# SparkFun_AST-CAN485_IO_Shield.net
KiCad netlist of a schematic drawn in EAGLE
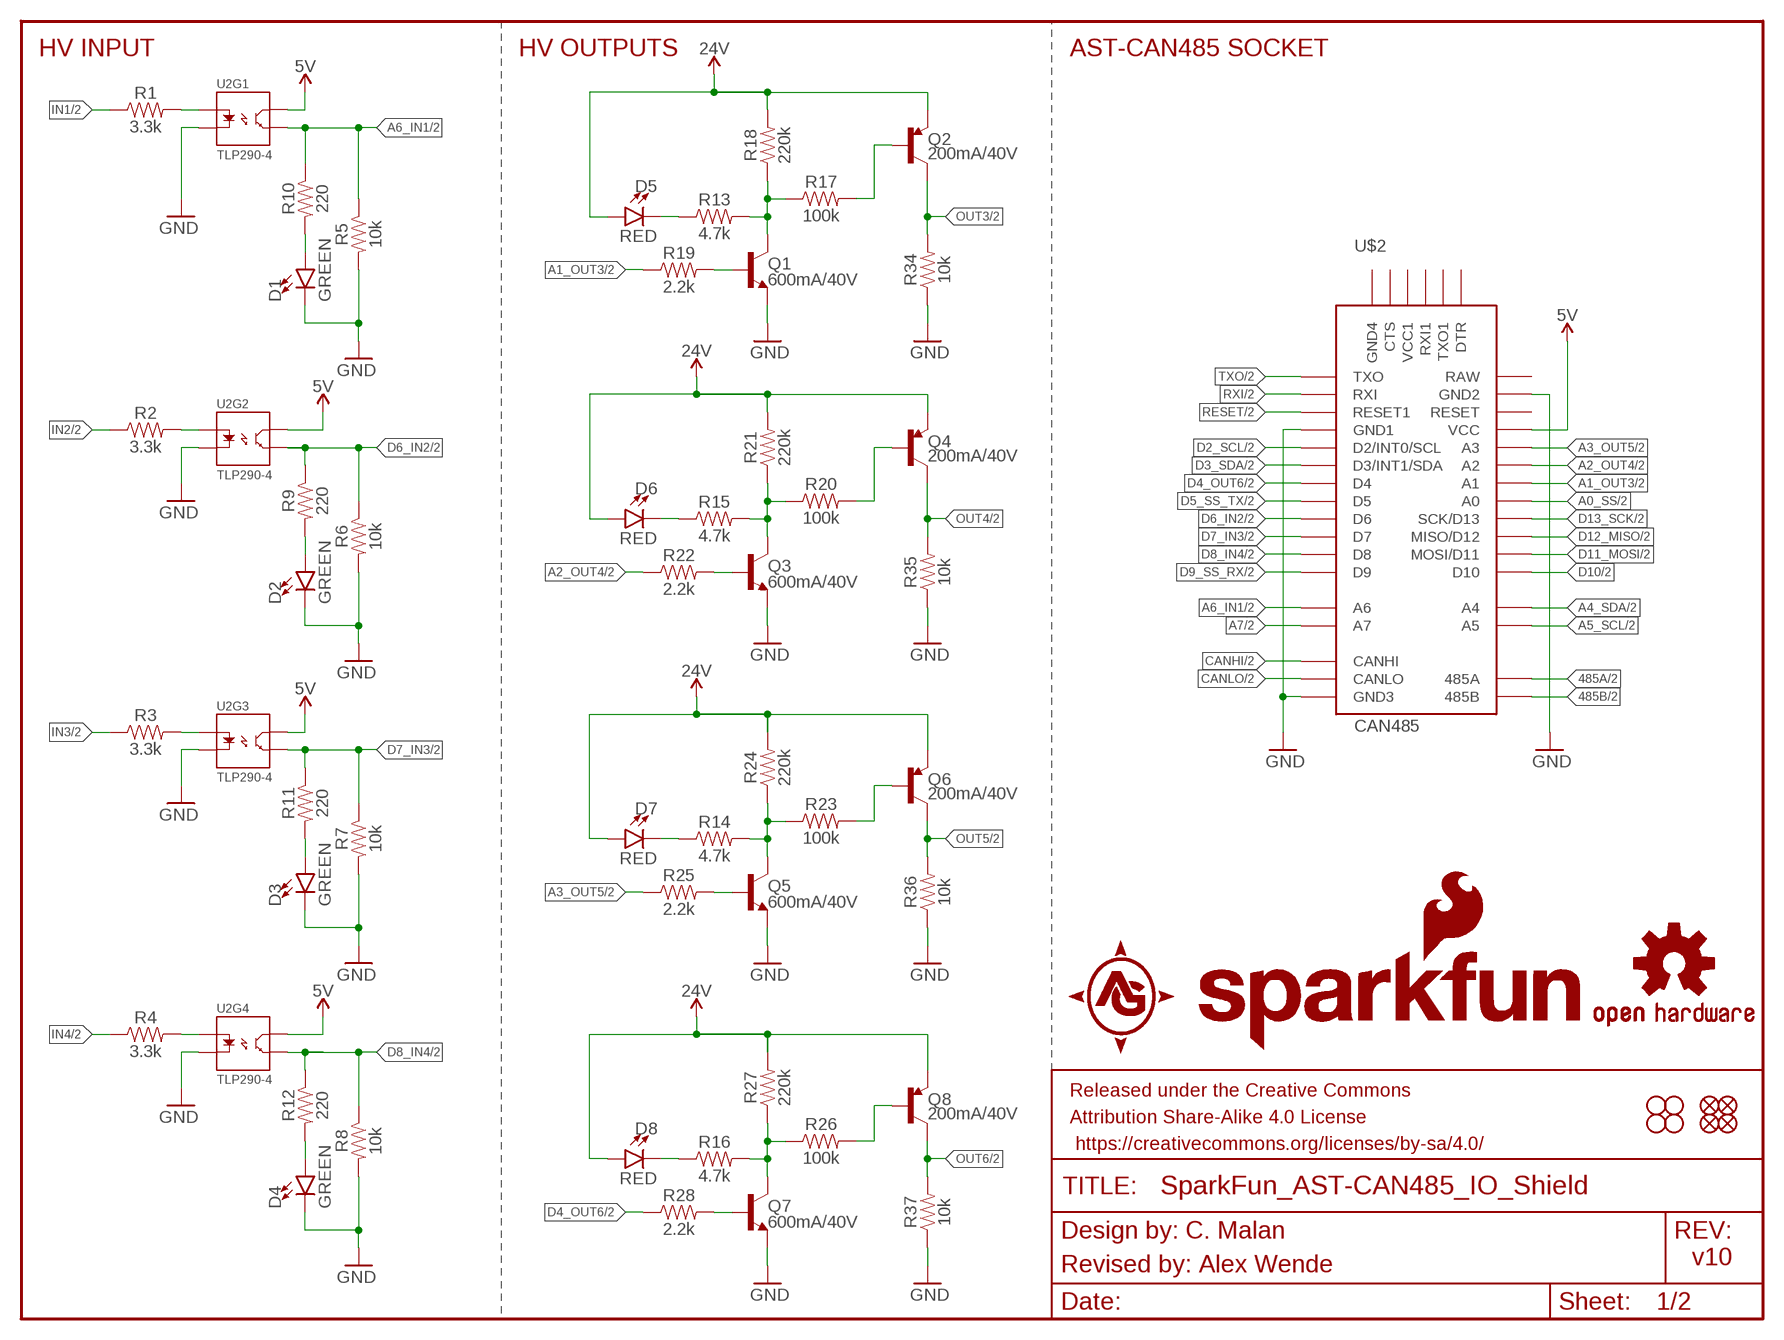
[diagram p0: schematic, sheet 1]
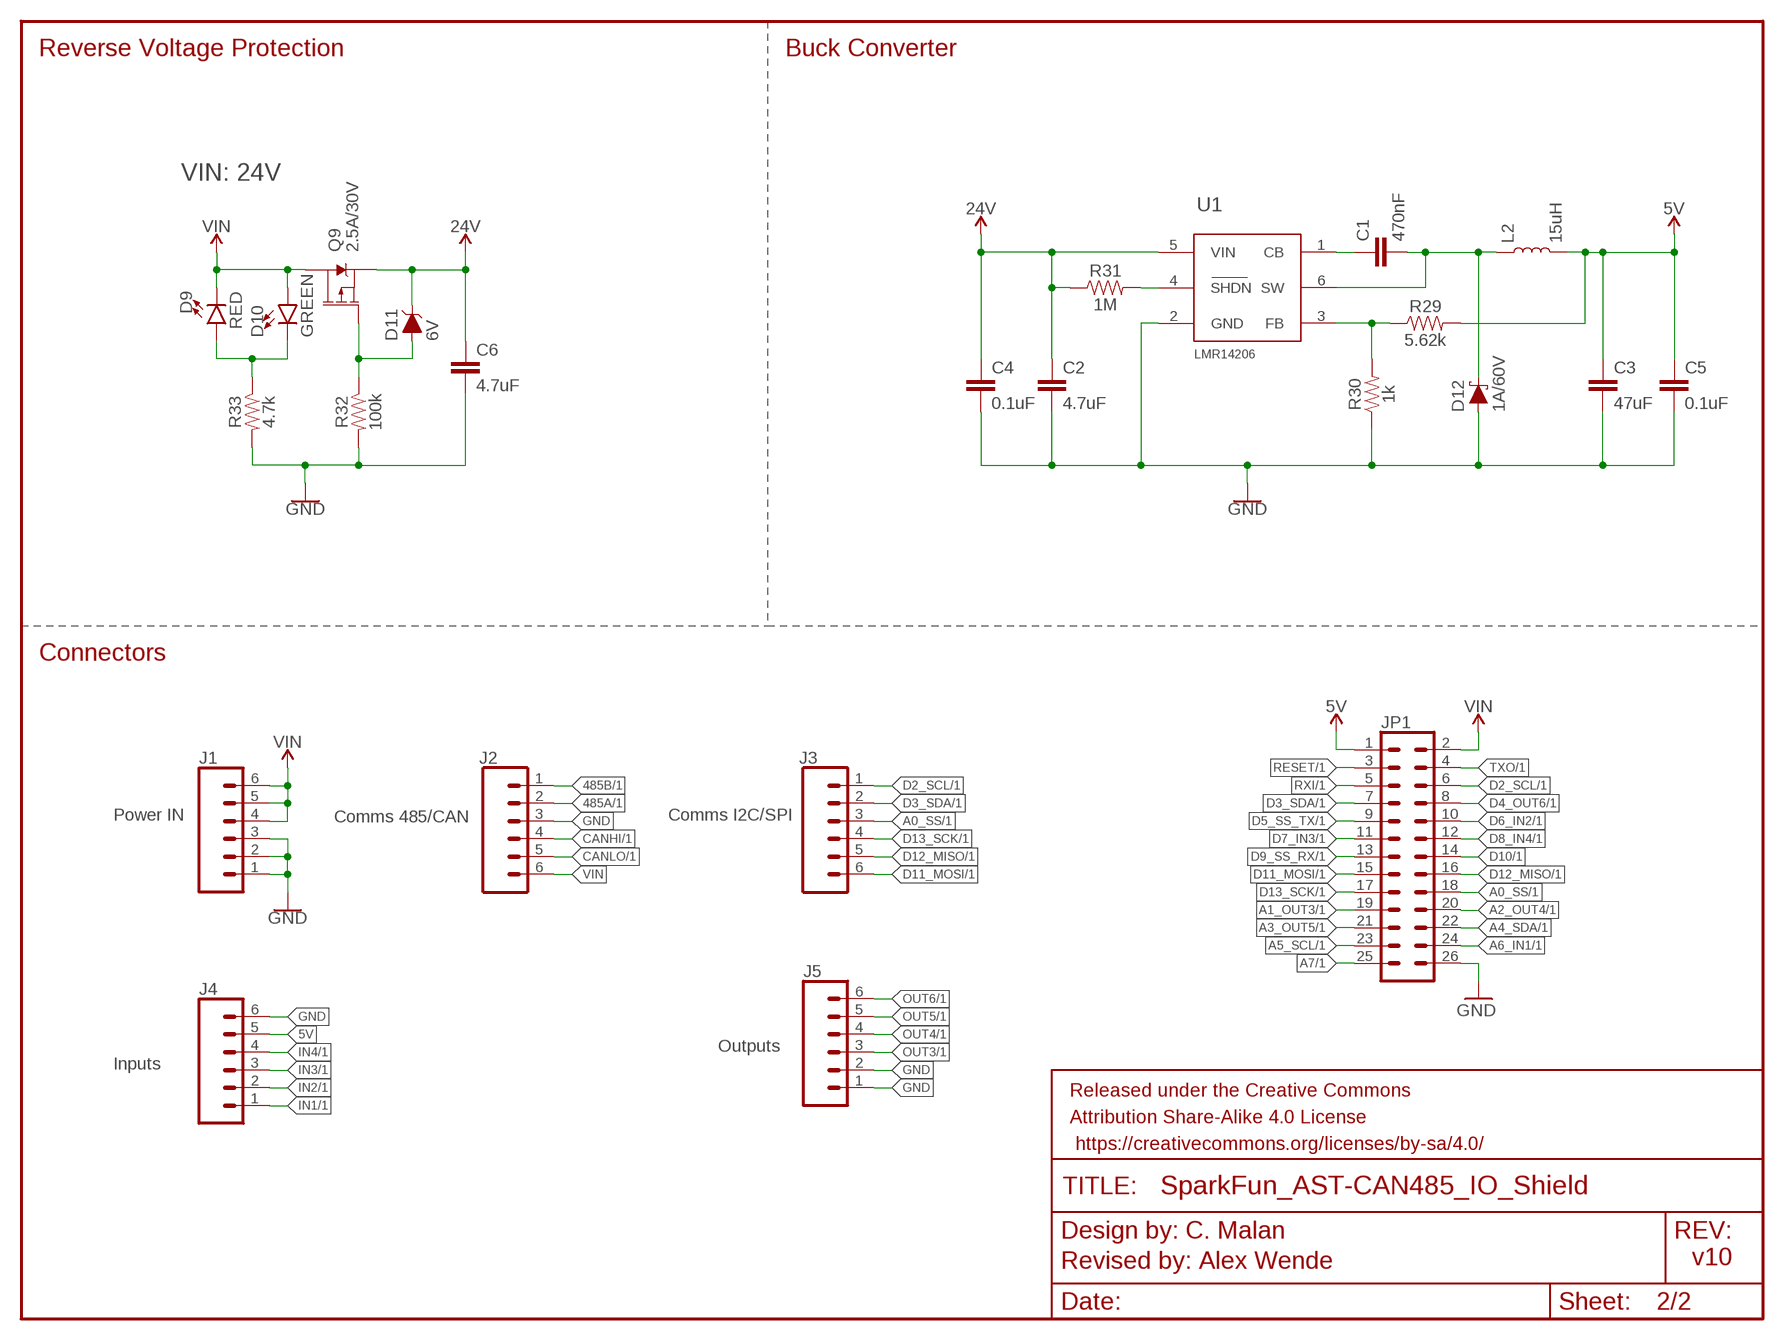
[diagram p1: schematic, sheet 2]

(export (version "E")
  (design (tool "Eeschema 10.0.6"))
  (components
    (comp (ref "D1")
      (value "GREEN")
      (footprint "eagle-import:LED-0603")
      (libsource (lib "eagle-import") (part "LED-GREEN0603"))
    )
    (comp (ref "D2")
      (value "GREEN")
      (footprint "eagle-import:LED-0603")
      (libsource (lib "eagle-import") (part "LED-GREEN0603"))
    )
    (comp (ref "D3")
      (value "GREEN")
      (footprint "eagle-import:LED-0603")
      (libsource (lib "eagle-import") (part "LED-GREEN0603"))
    )
    (comp (ref "D4")
      (value "GREEN")
      (footprint "eagle-import:LED-0603")
      (libsource (lib "eagle-import") (part "LED-GREEN0603"))
    )
    (comp (ref "D5")
      (value "RED")
      (footprint "eagle-import:LED-0603")
      (libsource (lib "eagle-import") (part "LED-RED0603"))
    )
    (comp (ref "D6")
      (value "RED")
      (footprint "eagle-import:LED-0603")
      (libsource (lib "eagle-import") (part "LED-RED0603"))
    )
    (comp (ref "D7")
      (value "RED")
      (footprint "eagle-import:LED-0603")
      (libsource (lib "eagle-import") (part "LED-RED0603"))
    )
    (comp (ref "D8")
      (value "RED")
      (footprint "eagle-import:LED-0603")
      (libsource (lib "eagle-import") (part "LED-RED0603"))
    )
    (comp (ref "FD1")
      (value "FIDUCIALUFIDUCIAL")
      (footprint "eagle-import:FIDUCIAL-MICRO")
      (libsource (lib "eagle-import") (part "FIDUCIALUFIDUCIAL"))
    )
    (comp (ref "FD2")
      (value "FIDUCIALUFIDUCIAL")
      (footprint "eagle-import:FIDUCIAL-MICRO")
      (libsource (lib "eagle-import") (part "FIDUCIALUFIDUCIAL"))
    )
    (comp (ref "FD3")
      (value "FIDUCIALUFIDUCIAL")
      (footprint "eagle-import:FIDUCIAL-MICRO")
      (libsource (lib "eagle-import") (part "FIDUCIALUFIDUCIAL"))
    )
    (comp (ref "FD4")
      (value "FIDUCIALUFIDUCIAL")
      (footprint "eagle-import:FIDUCIAL-MICRO")
      (libsource (lib "eagle-import") (part "FIDUCIALUFIDUCIAL"))
    )
    (comp (ref "FRAME3")
      (value "FRAME-LETTER")
      (footprint "eagle-import:CREATIVE_COMMONS")
      (libsource (lib "eagle-import") (part "FRAME-LETTER"))
    )
    (comp (ref "H1")
      (value "STAND-OFF")
      (footprint "eagle-import:STAND-OFF")
      (libsource (lib "eagle-import") (part "STAND-OFF"))
    )
    (comp (ref "H2")
      (value "STAND-OFF")
      (footprint "eagle-import:STAND-OFF")
      (libsource (lib "eagle-import") (part "STAND-OFF"))
    )
    (comp (ref "H3")
      (value "STAND-OFF")
      (footprint "eagle-import:STAND-OFF")
      (libsource (lib "eagle-import") (part "STAND-OFF"))
    )
    (comp (ref "H4")
      (value "STAND-OFF")
      (footprint "eagle-import:STAND-OFF")
      (libsource (lib "eagle-import") (part "STAND-OFF"))
    )
    (comp (ref "LOGO1")
      (value "OSHW-LOGOM")
      (footprint "eagle-import:OSHW-LOGO-M")
      (libsource (lib "eagle-import") (part "OSHW-LOGOM"))
    )
    (comp (ref "LOGO2")
      (value "SFE_LOGO_NAME_FLAME.2_INCH")
      (footprint "eagle-import:SFE_LOGO_NAME_FLAME_.2")
      (libsource (lib "eagle-import") (part "SFE_LOGO_NAME_FLAME.2_INCH"))
    )
    (comp (ref "Q1")
      (value "600mA/40V")
      (footprint "eagle-import:SOT23-3")
      (libsource (lib "eagle-import") (part "TRANS_NPN-MMBT2222AL"))
    )
    (comp (ref "Q2")
      (value "200mA/40V")
      (footprint "eagle-import:SOT23-3")
      (libsource (lib "eagle-import") (part "TRANS_PNP-PMBT3906|MMBT3906L"))
    )
    (comp (ref "Q3")
      (value "600mA/40V")
      (footprint "eagle-import:SOT23-3")
      (libsource (lib "eagle-import") (part "TRANS_NPN-MMBT2222AL"))
    )
    (comp (ref "Q4")
      (value "200mA/40V")
      (footprint "eagle-import:SOT23-3")
      (libsource (lib "eagle-import") (part "TRANS_PNP-PMBT3906|MMBT3906L"))
    )
    (comp (ref "Q5")
      (value "600mA/40V")
      (footprint "eagle-import:SOT23-3")
      (libsource (lib "eagle-import") (part "TRANS_NPN-MMBT2222AL"))
    )
    (comp (ref "Q6")
      (value "200mA/40V")
      (footprint "eagle-import:SOT23-3")
      (libsource (lib "eagle-import") (part "TRANS_PNP-PMBT3906|MMBT3906L"))
    )
    (comp (ref "Q7")
      (value "600mA/40V")
      (footprint "eagle-import:SOT23-3")
      (libsource (lib "eagle-import") (part "TRANS_NPN-MMBT2222AL"))
    )
    (comp (ref "Q8")
      (value "200mA/40V")
      (footprint "eagle-import:SOT23-3")
      (libsource (lib "eagle-import") (part "TRANS_PNP-PMBT3906|MMBT3906L"))
    )
    (comp (ref "R1")
      (value "3.3k")
      (footprint "eagle-import:0603")
      (libsource (lib "eagle-import") (part "3.3KOHM-0603-1/10W-1%"))
    )
    (comp (ref "R2")
      (value "3.3k")
      (footprint "eagle-import:0603")
      (libsource (lib "eagle-import") (part "3.3KOHM-0603-1/10W-1%"))
    )
    (comp (ref "R3")
      (value "3.3k")
      (footprint "eagle-import:0603")
      (libsource (lib "eagle-import") (part "3.3KOHM-0603-1/10W-1%"))
    )
    (comp (ref "R4")
      (value "3.3k")
      (footprint "eagle-import:0603")
      (libsource (lib "eagle-import") (part "3.3KOHM-0603-1/10W-1%"))
    )
    (comp (ref "R5")
      (value "10k")
      (footprint "eagle-import:0603")
      (libsource (lib "eagle-import") (part "10KOHM-0603-1/10W-1%"))
    )
    (comp (ref "R6")
      (value "10k")
      (footprint "eagle-import:0603")
      (libsource (lib "eagle-import") (part "10KOHM-0603-1/10W-1%"))
    )
    (comp (ref "R7")
      (value "10k")
      (footprint "eagle-import:0603")
      (libsource (lib "eagle-import") (part "10KOHM-0603-1/10W-1%"))
    )
    (comp (ref "R8")
      (value "10k")
      (footprint "eagle-import:0603")
      (libsource (lib "eagle-import") (part "10KOHM-0603-1/10W-1%"))
    )
    (comp (ref "R9")
      (value "220")
      (footprint "eagle-import:0603")
      (libsource (lib "eagle-import") (part "220OHM-0603-1/10W-1%"))
    )
    (comp (ref "R10")
      (value "220")
      (footprint "eagle-import:0603")
      (libsource (lib "eagle-import") (part "220OHM-0603-1/10W-1%"))
    )
    (comp (ref "R11")
      (value "220")
      (footprint "eagle-import:0603")
      (libsource (lib "eagle-import") (part "220OHM-0603-1/10W-1%"))
    )
    (comp (ref "R12")
      (value "220")
      (footprint "eagle-import:0603")
      (libsource (lib "eagle-import") (part "220OHM-0603-1/10W-1%"))
    )
    (comp (ref "R13")
      (value "4.7k")
      (footprint "eagle-import:0603")
      (libsource (lib "eagle-import") (part "4.7KOHM-0603-1/10W-1%"))
    )
    (comp (ref "R14")
      (value "4.7k")
      (footprint "eagle-import:0603")
      (libsource (lib "eagle-import") (part "4.7KOHM-0603-1/10W-1%"))
    )
    (comp (ref "R15")
      (value "4.7k")
      (footprint "eagle-import:0603")
      (libsource (lib "eagle-import") (part "4.7KOHM-0603-1/10W-1%"))
    )
    (comp (ref "R16")
      (value "4.7k")
      (footprint "eagle-import:0603")
      (libsource (lib "eagle-import") (part "4.7KOHM-0603-1/10W-1%"))
    )
    (comp (ref "R17")
      (value "100k")
      (footprint "eagle-import:0603")
      (libsource (lib "eagle-import") (part "100KOHM-0603-1/10W-1%"))
    )
    (comp (ref "R18")
      (value "220k")
      (footprint "eagle-import:0603")
      (libsource (lib "eagle-import") (part "220KOHM-0603-1/10W-1%"))
    )
    (comp (ref "R19")
      (value "2.2k")
      (footprint "eagle-import:0603")
      (libsource (lib "eagle-import") (part "2.2KOHM-0603-1/10W-1%"))
    )
    (comp (ref "R20")
      (value "100k")
      (footprint "eagle-import:0603")
      (libsource (lib "eagle-import") (part "100KOHM-0603-1/10W-1%"))
    )
    (comp (ref "R21")
      (value "220k")
      (footprint "eagle-import:0603")
      (libsource (lib "eagle-import") (part "220KOHM-0603-1/10W-1%"))
    )
    (comp (ref "R22")
      (value "2.2k")
      (footprint "eagle-import:0603")
      (libsource (lib "eagle-import") (part "2.2KOHM-0603-1/10W-1%"))
    )
    (comp (ref "R23")
      (value "100k")
      (footprint "eagle-import:0603")
      (libsource (lib "eagle-import") (part "100KOHM-0603-1/10W-1%"))
    )
    (comp (ref "R24")
      (value "220k")
      (footprint "eagle-import:0603")
      (libsource (lib "eagle-import") (part "220KOHM-0603-1/10W-1%"))
    )
    (comp (ref "R25")
      (value "2.2k")
      (footprint "eagle-import:0603")
      (libsource (lib "eagle-import") (part "2.2KOHM-0603-1/10W-1%"))
    )
    (comp (ref "R26")
      (value "100k")
      (footprint "eagle-import:0603")
      (libsource (lib "eagle-import") (part "100KOHM-0603-1/10W-1%"))
    )
    (comp (ref "R27")
      (value "220k")
      (footprint "eagle-import:0603")
      (libsource (lib "eagle-import") (part "220KOHM-0603-1/10W-1%"))
    )
    (comp (ref "R28")
      (value "2.2k")
      (footprint "eagle-import:0603")
      (libsource (lib "eagle-import") (part "2.2KOHM-0603-1/10W-1%"))
    )
    (comp (ref "R34")
      (value "10k")
      (footprint "eagle-import:0603")
      (libsource (lib "eagle-import") (part "10KOHM-0603-1/10W-1%"))
    )
    (comp (ref "R35")
      (value "10k")
      (footprint "eagle-import:0603")
      (libsource (lib "eagle-import") (part "10KOHM-0603-1/10W-1%"))
    )
    (comp (ref "R36")
      (value "10k")
      (footprint "eagle-import:0603")
      (libsource (lib "eagle-import") (part "10KOHM-0603-1/10W-1%"))
    )
    (comp (ref "R37")
      (value "10k")
      (footprint "eagle-import:0603")
      (libsource (lib "eagle-import") (part "10KOHM-0603-1/10W-1%"))
    )
    (comp (ref "U$2")
      (value "CAN485")
      (footprint "eagle-import:CAN485")
      (libsource (lib "eagle-import") (part "CAN485FULL_SOCKET"))
    )
    (comp (ref "U2")
      (value "TLP290-4")
      (footprint "eagle-import:SO16")
      (libsource (lib "eagle-import") (part "QUAD-OPTOISOLATOR"))
    )
    (comp (ref "C1")
      (value "470nF")
      (footprint "eagle-import:0603")
      (libsource (lib "eagle-import") (part "470NF-0603-10V-10%-X5R"))
    )
    (comp (ref "C2")
      (value "4.7uF")
      (footprint "eagle-import:0603")
      (libsource (lib "eagle-import") (part "4.7UF-0603-35V-(20%)"))
    )
    (comp (ref "C3")
      (value "47uF")
      (footprint "eagle-import:0805")
      (libsource (lib "eagle-import") (part "47UF"))
    )
    (comp (ref "C4")
      (value "0.1uF")
      (footprint "eagle-import:0603")
      (libsource (lib "eagle-import") (part "0.1UF-0603-100V-10%"))
    )
    (comp (ref "C5")
      (value "0.1uF")
      (footprint "eagle-import:0603")
      (libsource (lib "eagle-import") (part "0.1UF-0603-25V-(+80/-20%)"))
    )
    (comp (ref "C6")
      (value "4.7uF")
      (footprint "eagle-import:0603")
      (libsource (lib "eagle-import") (part "4.7UF-0603-35V-(20%)"))
    )
    (comp (ref "D9")
      (value "RED")
      (footprint "eagle-import:LED-0603")
      (libsource (lib "eagle-import") (part "LED-RED0603"))
    )
    (comp (ref "D10")
      (value "GREEN")
      (footprint "eagle-import:LED-0603")
      (libsource (lib "eagle-import") (part "LED-GREEN0603"))
    )
    (comp (ref "D11")
      (value "6V")
      (footprint "eagle-import:SOT23-3")
      (libsource (lib "eagle-import") (part "DIODE-ZENER-MMBZ5233BLT1G"))
    )
    (comp (ref "D12")
      (value "1A/60V")
      (footprint "eagle-import:DIODE-MICRO-SMP")
      (libsource (lib "eagle-import") (part "DIODE-SCHOTTKY-MSS1P6-M3/89A"))
    )
    (comp (ref "FRAME1")
      (value "FRAME-LETTERNO_PACKAGE")
      (footprint "eagle-import:DUMMY")
      (fields (field (name "DESIGNER") "Nobody"))
      (libsource (lib "eagle-import") (part "FRAME-LETTERNO_PACKAGE"))
    )
    (comp (ref "J1")
      (value "CONN_063.5MM-6")
      (footprint "eagle-import:SCREWTERMINAL-3.5MM-6")
      (libsource (lib "eagle-import") (part "CONN_063.5MM-6"))
    )
    (comp (ref "J2")
      (value "CONN_063.5MM-6")
      (footprint "eagle-import:SCREWTERMINAL-3.5MM-6")
      (libsource (lib "eagle-import") (part "CONN_063.5MM-6"))
    )
    (comp (ref "J3")
      (value "CONN_063.5MM-6")
      (footprint "eagle-import:SCREWTERMINAL-3.5MM-6")
      (libsource (lib "eagle-import") (part "CONN_063.5MM-6"))
    )
    (comp (ref "J4")
      (value "CONN_063.5MM-6")
      (footprint "eagle-import:SCREWTERMINAL-3.5MM-6")
      (libsource (lib "eagle-import") (part "CONN_063.5MM-6"))
    )
    (comp (ref "J5")
      (value "CONN_063.5MM-6")
      (footprint "eagle-import:SCREWTERMINAL-3.5MM-6")
      (libsource (lib "eagle-import") (part "CONN_063.5MM-6"))
    )
    (comp (ref "JP1")
      (value "CONN_13X22X13")
      (footprint "eagle-import:2X13")
      (libsource (lib "eagle-import") (part "CONN_13X22X13"))
    )
    (comp (ref "L2")
      (value "15uH")
      (footprint "eagle-import:INDUCTOR_LQH32")
      (libsource (lib "eagle-import") (part "INDUCTOR-LHQ32-15UH"))
    )
    (comp (ref "Q9")
      (value "2.5A/30V")
      (footprint "eagle-import:SOT23-3")
      (libsource (lib "eagle-import") (part "MOSFET_PCH-DMG2307L"))
    )
    (comp (ref "R29")
      (value "5.62k")
      (footprint "eagle-import:0603")
      (libsource (lib "eagle-import") (part "5.62KOHM-0603-1/10W-1%"))
    )
    (comp (ref "R30")
      (value "1k")
      (footprint "eagle-import:0603")
      (libsource (lib "eagle-import") (part "1KOHM-0603-1/10W-1%"))
    )
    (comp (ref "R31")
      (value "1M")
      (footprint "eagle-import:0603")
      (libsource (lib "eagle-import") (part "1MOHM-0603-1/4W-5%"))
    )
    (comp (ref "R32")
      (value "100k")
      (footprint "eagle-import:0603")
      (libsource (lib "eagle-import") (part "100KOHM-0603-1/10W-1%"))
    )
    (comp (ref "R33")
      (value "4.7k")
      (footprint "eagle-import:0603")
      (libsource (lib "eagle-import") (part "4.7KOHM-0603-1/10W-1%"))
    )
    (comp (ref "U1")
      (value "LMR14206")
      (footprint "eagle-import:SOT23-6")
      (libsource (lib "eagle-import") (part "LMR14203"))
    )
  )
  (nets
    (net (code "1") (name "5V") (class "Default")
      (node (ref "C3") (pin "1") (pinfunction "1_1") (pintype "passive"))
      (node (ref "C5") (pin "1") (pinfunction "1_1") (pintype "passive"))
      (node (ref "J4") (pin "5") (pinfunction "5_5") (pintype "passive"))
      (node (ref "JP1") (pin "1") (pinfunction "1_1") (pintype "passive"))
      (node (ref "L2") (pin "P$2") (pinfunction "2_P$2") (pintype "passive"))
      (node (ref "R29") (pin "2") (pinfunction "2_2") (pintype "passive"))
      (node (ref "U$2") (pin "VCC") (pinfunction "VCC_VCC") (pintype "bidirectional"))
      (node (ref "U2") (pin "10") (pinfunction "CL1_10") (pintype "bidirectional"))
      (node (ref "U2") (pin "12") (pinfunction "CL1_12") (pintype "bidirectional"))
      (node (ref "U2") (pin "14") (pinfunction "CL1_14") (pintype "bidirectional"))
      (node (ref "U2") (pin "16") (pinfunction "CL1_16") (pintype "bidirectional"))
    )
    (net (code "2") (name "24V") (class "Default")
      (node (ref "C2") (pin "1") (pinfunction "1_1") (pintype "passive"))
      (node (ref "C4") (pin "1") (pinfunction "1_1") (pintype "passive"))
      (node (ref "C6") (pin "1") (pinfunction "1_1") (pintype "passive"))
      (node (ref "D11") (pin "3") (pinfunction "C_3") (pintype "passive"))
      (node (ref "D5") (pin "A") (pinfunction "A_A") (pintype "passive"))
      (node (ref "D6") (pin "A") (pinfunction "A_A") (pintype "passive"))
      (node (ref "D7") (pin "A") (pinfunction "A_A") (pintype "passive"))
      (node (ref "D8") (pin "A") (pinfunction "A_A") (pintype "passive"))
      (node (ref "Q2") (pin "2") (pinfunction "E_2") (pintype "passive"))
      (node (ref "Q4") (pin "2") (pinfunction "E_2") (pintype "passive"))
      (node (ref "Q6") (pin "2") (pinfunction "E_2") (pintype "passive"))
      (node (ref "Q8") (pin "2") (pinfunction "E_2") (pintype "passive"))
      (node (ref "Q9") (pin "2") (pinfunction "S_2") (pintype "bidirectional"))
      (node (ref "R18") (pin "2") (pinfunction "2_2") (pintype "passive"))
      (node (ref "R21") (pin "2") (pinfunction "2_2") (pintype "passive"))
      (node (ref "R24") (pin "2") (pinfunction "2_2") (pintype "passive"))
      (node (ref "R27") (pin "2") (pinfunction "2_2") (pintype "passive"))
      (node (ref "R31") (pin "1") (pinfunction "1_1") (pintype "passive"))
      (node (ref "U1") (pin "5") (pinfunction "VIN_5") (pintype "power_in"))
    )
    (net (code "3") (name "485A") (class "Default")
      (node (ref "J2") (pin "2") (pinfunction "2_2") (pintype "passive"))
      (node (ref "U$2") (pin "485A") (pinfunction "485A_485A") (pintype "bidirectional"))
    )
    (net (code "4") (name "485B") (class "Default")
      (node (ref "J2") (pin "1") (pinfunction "1_1") (pintype "passive"))
      (node (ref "U$2") (pin "485B") (pinfunction "485B_485B") (pintype "bidirectional"))
    )
    (net (code "5") (name "A0_SS") (class "Default")
      (node (ref "J3") (pin "3") (pinfunction "3_3") (pintype "passive"))
      (node (ref "JP1") (pin "18") (pinfunction "18_18") (pintype "passive"))
      (node (ref "U$2") (pin "A0") (pinfunction "A0_A0") (pintype "bidirectional"))
    )
    (net (code "6") (name "A1_OUT3") (class "Default")
      (node (ref "JP1") (pin "19") (pinfunction "19_19") (pintype "passive"))
      (node (ref "R19") (pin "1") (pinfunction "1_1") (pintype "passive"))
      (node (ref "U$2") (pin "A1") (pinfunction "A1_A1") (pintype "bidirectional"))
    )
    (net (code "7") (name "A2_OUT4") (class "Default")
      (node (ref "JP1") (pin "20") (pinfunction "20_20") (pintype "passive"))
      (node (ref "R22") (pin "1") (pinfunction "1_1") (pintype "passive"))
      (node (ref "U$2") (pin "A2") (pinfunction "A2_A2") (pintype "bidirectional"))
    )
    (net (code "8") (name "A3_OUT5") (class "Default")
      (node (ref "JP1") (pin "21") (pinfunction "21_21") (pintype "passive"))
      (node (ref "R25") (pin "1") (pinfunction "1_1") (pintype "passive"))
      (node (ref "U$2") (pin "A3") (pinfunction "A3_A3") (pintype "bidirectional"))
    )
    (net (code "9") (name "A4_SDA") (class "Default")
      (node (ref "JP1") (pin "22") (pinfunction "22_22") (pintype "passive"))
      (node (ref "U$2") (pin "A4") (pinfunction "A4_A4") (pintype "bidirectional"))
    )
    (net (code "10") (name "A5_SCL") (class "Default")
      (node (ref "JP1") (pin "23") (pinfunction "23_23") (pintype "passive"))
      (node (ref "U$2") (pin "A5") (pinfunction "A5_A5") (pintype "bidirectional"))
    )
    (net (code "11") (name "A6_IN1") (class "Default")
      (node (ref "JP1") (pin "24") (pinfunction "24_24") (pintype "passive"))
      (node (ref "R10") (pin "1") (pinfunction "1_1") (pintype "passive"))
      (node (ref "R5") (pin "1") (pinfunction "1_1") (pintype "passive"))
      (node (ref "U$2") (pin "A6") (pinfunction "A6_A6") (pintype "bidirectional"))
      (node (ref "U2") (pin "15") (pinfunction "EM1_15") (pintype "bidirectional"))
    )
    (net (code "12") (name "A7") (class "Default")
      (node (ref "JP1") (pin "25") (pinfunction "25_25") (pintype "passive"))
      (node (ref "U$2") (pin "A7") (pinfunction "A7_A7") (pintype "bidirectional"))
    )
    (net (code "13") (name "CANHI") (class "Default")
      (node (ref "J2") (pin "4") (pinfunction "4_4") (pintype "passive"))
      (node (ref "U$2") (pin "CANHI") (pinfunction "CANHI_CANHI") (pintype "bidirectional"))
    )
    (net (code "14") (name "CANLO") (class "Default")
      (node (ref "J2") (pin "5") (pinfunction "5_5") (pintype "passive"))
      (node (ref "U$2") (pin "CANLO") (pinfunction "CANLO_CANLO") (pintype "bidirectional"))
    )
    (net (code "15") (name "D2_SCL") (class "Default")
      (node (ref "J3") (pin "1") (pinfunction "1_1") (pintype "passive"))
      (node (ref "JP1") (pin "6") (pinfunction "6_6") (pintype "passive"))
      (node (ref "U$2") (pin "2") (pinfunction "D2/INT0/SCL_2") (pintype "bidirectional"))
    )
    (net (code "16") (name "D3_SDA") (class "Default")
      (node (ref "J3") (pin "2") (pinfunction "2_2") (pintype "passive"))
      (node (ref "JP1") (pin "7") (pinfunction "7_7") (pintype "passive"))
      (node (ref "U$2") (pin "3") (pinfunction "D3/INT1/SDA_3") (pintype "bidirectional"))
    )
    (net (code "17") (name "D4_OUT6") (class "Default")
      (node (ref "JP1") (pin "8") (pinfunction "8_8") (pintype "passive"))
      (node (ref "R28") (pin "1") (pinfunction "1_1") (pintype "passive"))
      (node (ref "U$2") (pin "4") (pinfunction "D4_4") (pintype "bidirectional"))
    )
    (net (code "18") (name "D5_SS_TX") (class "Default")
      (node (ref "JP1") (pin "9") (pinfunction "9_9") (pintype "passive"))
      (node (ref "U$2") (pin "5") (pinfunction "D5_5") (pintype "bidirectional"))
    )
    (net (code "19") (name "D6_IN2") (class "Default")
      (node (ref "JP1") (pin "10") (pinfunction "10_10") (pintype "passive"))
      (node (ref "R6") (pin "1") (pinfunction "1_1") (pintype "passive"))
      (node (ref "R9") (pin "1") (pinfunction "1_1") (pintype "passive"))
      (node (ref "U$2") (pin "6") (pinfunction "D6_6") (pintype "bidirectional"))
      (node (ref "U2") (pin "13") (pinfunction "EM1_13") (pintype "bidirectional"))
    )
    (net (code "20") (name "D7_IN3") (class "Default")
      (node (ref "JP1") (pin "11") (pinfunction "11_11") (pintype "passive"))
      (node (ref "R11") (pin "1") (pinfunction "1_1") (pintype "passive"))
      (node (ref "R7") (pin "1") (pinfunction "1_1") (pintype "passive"))
      (node (ref "U$2") (pin "7") (pinfunction "D7_7") (pintype "bidirectional"))
      (node (ref "U2") (pin "11") (pinfunction "EM1_11") (pintype "bidirectional"))
    )
    (net (code "21") (name "D8_IN4") (class "Default")
      (node (ref "JP1") (pin "12") (pinfunction "12_12") (pintype "passive"))
      (node (ref "R12") (pin "1") (pinfunction "1_1") (pintype "passive"))
      (node (ref "R8") (pin "1") (pinfunction "1_1") (pintype "passive"))
      (node (ref "U$2") (pin "8") (pinfunction "D8_8") (pintype "bidirectional"))
      (node (ref "U2") (pin "9") (pinfunction "EM1_9") (pintype "bidirectional"))
    )
    (net (code "22") (name "D9_SS_RX") (class "Default")
      (node (ref "JP1") (pin "13") (pinfunction "13_13") (pintype "passive"))
      (node (ref "U$2") (pin "9") (pinfunction "D9_9") (pintype "bidirectional"))
    )
    (net (code "23") (name "D10") (class "Default")
      (node (ref "JP1") (pin "14") (pinfunction "14_14") (pintype "passive"))
      (node (ref "U$2") (pin "10") (pinfunction "D10_10") (pintype "bidirectional"))
    )
    (net (code "24") (name "D11_MOSI") (class "Default")
      (node (ref "J3") (pin "6") (pinfunction "6_6") (pintype "passive"))
      (node (ref "JP1") (pin "15") (pinfunction "15_15") (pintype "passive"))
      (node (ref "U$2") (pin "11") (pinfunction "MOSI/D11_11") (pintype "bidirectional"))
    )
    (net (code "25") (name "D12_MISO") (class "Default")
      (node (ref "J3") (pin "5") (pinfunction "5_5") (pintype "passive"))
      (node (ref "JP1") (pin "16") (pinfunction "16_16") (pintype "passive"))
      (node (ref "U$2") (pin "12") (pinfunction "MISO/D12_12") (pintype "bidirectional"))
    )
    (net (code "26") (name "D13_SCK") (class "Default")
      (node (ref "J3") (pin "4") (pinfunction "4_4") (pintype "passive"))
      (node (ref "JP1") (pin "17") (pinfunction "17_17") (pintype "passive"))
      (node (ref "U$2") (pin "13") (pinfunction "SCK/D13_13") (pintype "bidirectional"))
    )
    (net (code "27") (name "GND") (class "Default")
      (node (ref "C2") (pin "2") (pinfunction "2_2") (pintype "passive"))
      (node (ref "C3") (pin "2") (pinfunction "2_2") (pintype "passive"))
      (node (ref "C4") (pin "2") (pinfunction "2_2") (pintype "passive"))
      (node (ref "C5") (pin "2") (pinfunction "2_2") (pintype "passive"))
      (node (ref "C6") (pin "2") (pinfunction "2_2") (pintype "passive"))
      (node (ref "D1") (pin "C") (pinfunction "C_C") (pintype "passive"))
      (node (ref "D12") (pin "A") (pinfunction "A_A") (pintype "passive"))
      (node (ref "D2") (pin "C") (pinfunction "C_C") (pintype "passive"))
      (node (ref "D3") (pin "C") (pinfunction "C_C") (pintype "passive"))
      (node (ref "D4") (pin "C") (pinfunction "C_C") (pintype "passive"))
      (node (ref "J1") (pin "1") (pinfunction "1_1") (pintype "passive"))
      (node (ref "J1") (pin "2") (pinfunction "2_2") (pintype "passive"))
      (node (ref "J1") (pin "3") (pinfunction "3_3") (pintype "passive"))
      (node (ref "J2") (pin "3") (pinfunction "3_3") (pintype "passive"))
      (node (ref "J4") (pin "6") (pinfunction "6_6") (pintype "passive"))
      (node (ref "J5") (pin "1") (pinfunction "1_1") (pintype "passive"))
      (node (ref "J5") (pin "2") (pinfunction "2_2") (pintype "passive"))
      (node (ref "JP1") (pin "26") (pinfunction "26_26") (pintype "passive"))
      (node (ref "Q1") (pin "2") (pinfunction "E_2") (pintype "passive"))
      (node (ref "Q3") (pin "2") (pinfunction "E_2") (pintype "passive"))
      (node (ref "Q5") (pin "2") (pinfunction "E_2") (pintype "passive"))
      (node (ref "Q7") (pin "2") (pinfunction "E_2") (pintype "passive"))
      (node (ref "R30") (pin "1") (pinfunction "1_1") (pintype "passive"))
      (node (ref "R32") (pin "2") (pinfunction "2_2") (pintype "passive"))
      (node (ref "R33") (pin "2") (pinfunction "2_2") (pintype "passive"))
      (node (ref "R34") (pin "1") (pinfunction "1_1") (pintype "passive"))
      (node (ref "R35") (pin "1") (pinfunction "1_1") (pintype "passive"))
      (node (ref "R36") (pin "1") (pinfunction "1_1") (pintype "passive"))
      (node (ref "R37") (pin "1") (pinfunction "1_1") (pintype "passive"))
      (node (ref "R5") (pin "2") (pinfunction "2_2") (pintype "passive"))
      (node (ref "R6") (pin "2") (pinfunction "2_2") (pintype "passive"))
      (node (ref "R7") (pin "2") (pinfunction "2_2") (pintype "passive"))
      (node (ref "R8") (pin "2") (pinfunction "2_2") (pintype "passive"))
      (node (ref "U$2") (pin "GND1") (pinfunction "GND1_GND1") (pintype "bidirectional"))
      (node (ref "U$2") (pin "GND2") (pinfunction "GND2_GND2") (pintype "bidirectional"))
      (node (ref "U$2") (pin "GND3") (pinfunction "GND3_GND3") (pintype "bidirectional"))
      (node (ref "U1") (pin "2") (pinfunction "GND_2") (pintype "power_in"))
      (node (ref "U2") (pin "2") (pinfunction "C1_2") (pintype "bidirectional"))
      (node (ref "U2") (pin "4") (pinfunction "C1_4") (pintype "bidirectional"))
      (node (ref "U2") (pin "6") (pinfunction "C1_6") (pintype "bidirectional"))
      (node (ref "U2") (pin "8") (pinfunction "C1_8") (pintype "bidirectional"))
    )
    (net (code "28") (name "IN1") (class "Default")
      (node (ref "J4") (pin "1") (pinfunction "1_1") (pintype "passive"))
      (node (ref "R1") (pin "1") (pinfunction "1_1") (pintype "passive"))
    )
    (net (code "29") (name "IN2") (class "Default")
      (node (ref "J4") (pin "2") (pinfunction "2_2") (pintype "passive"))
      (node (ref "R2") (pin "1") (pinfunction "1_1") (pintype "passive"))
    )
    (net (code "30") (name "IN3") (class "Default")
      (node (ref "J4") (pin "3") (pinfunction "3_3") (pintype "passive"))
      (node (ref "R3") (pin "1") (pinfunction "1_1") (pintype "passive"))
    )
    (net (code "31") (name "IN4") (class "Default")
      (node (ref "J4") (pin "4") (pinfunction "4_4") (pintype "passive"))
      (node (ref "R4") (pin "1") (pinfunction "1_1") (pintype "passive"))
    )
    (net (code "32") (name "Net-(D1-PadA)") (class "Default")
      (node (ref "D1") (pin "A") (pinfunction "A_A") (pintype "passive"))
      (node (ref "R10") (pin "2") (pinfunction "2_2") (pintype "passive"))
    )
    (net (code "33") (name "Net-(D2-PadA)") (class "Default")
      (node (ref "D2") (pin "A") (pinfunction "A_A") (pintype "passive"))
      (node (ref "R9") (pin "2") (pinfunction "2_2") (pintype "passive"))
    )
    (net (code "34") (name "Net-(D3-PadA)") (class "Default")
      (node (ref "D3") (pin "A") (pinfunction "A_A") (pintype "passive"))
      (node (ref "R11") (pin "2") (pinfunction "2_2") (pintype "passive"))
    )
    (net (code "35") (name "Net-(D4-PadA)") (class "Default")
      (node (ref "D4") (pin "A") (pinfunction "A_A") (pintype "passive"))
      (node (ref "R12") (pin "2") (pinfunction "2_2") (pintype "passive"))
    )
    (net (code "36") (name "Net-(D5-PadC)") (class "Default")
      (node (ref "D5") (pin "C") (pinfunction "C_C") (pintype "passive"))
      (node (ref "R13") (pin "1") (pinfunction "1_1") (pintype "passive"))
    )
    (net (code "37") (name "Net-(D6-PadC)") (class "Default")
      (node (ref "D6") (pin "C") (pinfunction "C_C") (pintype "passive"))
      (node (ref "R15") (pin "1") (pinfunction "1_1") (pintype "passive"))
    )
    (net (code "38") (name "Net-(D7-PadC)") (class "Default")
      (node (ref "D7") (pin "C") (pinfunction "C_C") (pintype "passive"))
      (node (ref "R14") (pin "1") (pinfunction "1_1") (pintype "passive"))
    )
    (net (code "39") (name "Net-(D8-PadC)") (class "Default")
      (node (ref "D8") (pin "C") (pinfunction "C_C") (pintype "passive"))
      (node (ref "R16") (pin "1") (pinfunction "1_1") (pintype "passive"))
    )
    (net (code "40") (name "Net-(D10-PadC)") (class "Default")
      (node (ref "D10") (pin "C") (pinfunction "C_C") (pintype "passive"))
      (node (ref "D9") (pin "A") (pinfunction "A_A") (pintype "passive"))
      (node (ref "R33") (pin "1") (pinfunction "1_1") (pintype "passive"))
    )
    (net (code "41") (name "Net-(D11-A)") (class "Default")
      (node (ref "D11") (pin "1") (pinfunction "A_1") (pintype "passive"))
      (node (ref "Q9") (pin "1") (pinfunction "G_1") (pintype "bidirectional"))
      (node (ref "R32") (pin "1") (pinfunction "1_1") (pintype "passive"))
    )
    (net (code "42") (name "Net-(L2-1)") (class "Default")
      (node (ref "C1") (pin "2") (pinfunction "2_2") (pintype "passive"))
      (node (ref "D12") (pin "C") (pinfunction "C_C") (pintype "passive"))
      (node (ref "L2") (pin "P$1") (pinfunction "1_P$1") (pintype "passive"))
      (node (ref "U1") (pin "6") (pinfunction "SW_6") (pintype "power_in"))
    )
    (net (code "43") (name "Net-(Q1-B)") (class "Default")
      (node (ref "Q1") (pin "1") (pinfunction "B_1") (pintype "passive"))
      (node (ref "R19") (pin "2") (pinfunction "2_2") (pintype "passive"))
    )
    (net (code "44") (name "Net-(Q1-C)") (class "Default")
      (node (ref "Q1") (pin "3") (pinfunction "C_3") (pintype "passive"))
      (node (ref "R13") (pin "2") (pinfunction "2_2") (pintype "passive"))
      (node (ref "R17") (pin "1") (pinfunction "1_1") (pintype "passive"))
      (node (ref "R18") (pin "1") (pinfunction "1_1") (pintype "passive"))
    )
    (net (code "45") (name "Net-(Q2-B)") (class "Default")
      (node (ref "Q2") (pin "1") (pinfunction "B_1") (pintype "passive"))
      (node (ref "R17") (pin "2") (pinfunction "2_2") (pintype "passive"))
    )
    (net (code "46") (name "Net-(Q3-B)") (class "Default")
      (node (ref "Q3") (pin "1") (pinfunction "B_1") (pintype "passive"))
      (node (ref "R22") (pin "2") (pinfunction "2_2") (pintype "passive"))
    )
    (net (code "47") (name "Net-(Q3-C)") (class "Default")
      (node (ref "Q3") (pin "3") (pinfunction "C_3") (pintype "passive"))
      (node (ref "R15") (pin "2") (pinfunction "2_2") (pintype "passive"))
      (node (ref "R20") (pin "1") (pinfunction "1_1") (pintype "passive"))
      (node (ref "R21") (pin "1") (pinfunction "1_1") (pintype "passive"))
    )
    (net (code "48") (name "Net-(Q4-B)") (class "Default")
      (node (ref "Q4") (pin "1") (pinfunction "B_1") (pintype "passive"))
      (node (ref "R20") (pin "2") (pinfunction "2_2") (pintype "passive"))
    )
    (net (code "49") (name "Net-(Q5-B)") (class "Default")
      (node (ref "Q5") (pin "1") (pinfunction "B_1") (pintype "passive"))
      (node (ref "R25") (pin "2") (pinfunction "2_2") (pintype "passive"))
    )
    (net (code "50") (name "Net-(Q5-C)") (class "Default")
      (node (ref "Q5") (pin "3") (pinfunction "C_3") (pintype "passive"))
      (node (ref "R14") (pin "2") (pinfunction "2_2") (pintype "passive"))
      (node (ref "R23") (pin "1") (pinfunction "1_1") (pintype "passive"))
      (node (ref "R24") (pin "1") (pinfunction "1_1") (pintype "passive"))
    )
    (net (code "51") (name "Net-(Q6-B)") (class "Default")
      (node (ref "Q6") (pin "1") (pinfunction "B_1") (pintype "passive"))
      (node (ref "R23") (pin "2") (pinfunction "2_2") (pintype "passive"))
    )
    (net (code "52") (name "Net-(Q7-B)") (class "Default")
      (node (ref "Q7") (pin "1") (pinfunction "B_1") (pintype "passive"))
      (node (ref "R28") (pin "2") (pinfunction "2_2") (pintype "passive"))
    )
    (net (code "53") (name "Net-(Q7-C)") (class "Default")
      (node (ref "Q7") (pin "3") (pinfunction "C_3") (pintype "passive"))
      (node (ref "R16") (pin "2") (pinfunction "2_2") (pintype "passive"))
      (node (ref "R26") (pin "1") (pinfunction "1_1") (pintype "passive"))
      (node (ref "R27") (pin "1") (pinfunction "1_1") (pintype "passive"))
    )
    (net (code "54") (name "Net-(Q8-B)") (class "Default")
      (node (ref "Q8") (pin "1") (pinfunction "B_1") (pintype "passive"))
      (node (ref "R26") (pin "2") (pinfunction "2_2") (pintype "passive"))
    )
    (net (code "55") (name "Net-(U1-CB)") (class "Default")
      (node (ref "C1") (pin "1") (pinfunction "1_1") (pintype "passive"))
      (node (ref "U1") (pin "1") (pinfunction "CB_1") (pintype "input"))
    )
    (net (code "56") (name "Net-(U1-FB)") (class "Default")
      (node (ref "R29") (pin "1") (pinfunction "1_1") (pintype "passive"))
      (node (ref "R30") (pin "2") (pinfunction "2_2") (pintype "passive"))
      (node (ref "U1") (pin "3") (pinfunction "FB_3") (pintype "input"))
    )
    (net (code "57") (name "Net-(U1-SHDN)") (class "Default")
      (node (ref "R31") (pin "2") (pinfunction "2_2") (pintype "passive"))
      (node (ref "U1") (pin "4") (pinfunction "SHDN_4") (pintype "input"))
    )
    (net (code "58") (name "Net-(U2A-A1)") (class "Default")
      (node (ref "R1") (pin "2") (pinfunction "2_2") (pintype "passive"))
      (node (ref "U2") (pin "1") (pinfunction "A1_1") (pintype "bidirectional"))
    )
    (net (code "59") (name "Net-(U2B-A1)") (class "Default")
      (node (ref "R2") (pin "2") (pinfunction "2_2") (pintype "passive"))
      (node (ref "U2") (pin "3") (pinfunction "A1_3") (pintype "bidirectional"))
    )
    (net (code "60") (name "Net-(U2C-A1)") (class "Default")
      (node (ref "R3") (pin "2") (pinfunction "2_2") (pintype "passive"))
      (node (ref "U2") (pin "5") (pinfunction "A1_5") (pintype "bidirectional"))
    )
    (net (code "61") (name "Net-(U2D-A1)") (class "Default")
      (node (ref "R4") (pin "2") (pinfunction "2_2") (pintype "passive"))
      (node (ref "U2") (pin "7") (pinfunction "A1_7") (pintype "bidirectional"))
    )
    (net (code "62") (name "OUT3") (class "Default")
      (node (ref "J5") (pin "3") (pinfunction "3_3") (pintype "passive"))
      (node (ref "Q2") (pin "3") (pinfunction "C_3") (pintype "passive"))
      (node (ref "R34") (pin "2") (pinfunction "2_2") (pintype "passive"))
    )
    (net (code "63") (name "OUT4") (class "Default")
      (node (ref "J5") (pin "4") (pinfunction "4_4") (pintype "passive"))
      (node (ref "Q4") (pin "3") (pinfunction "C_3") (pintype "passive"))
      (node (ref "R35") (pin "2") (pinfunction "2_2") (pintype "passive"))
    )
    (net (code "64") (name "OUT5") (class "Default")
      (node (ref "J5") (pin "5") (pinfunction "5_5") (pintype "passive"))
      (node (ref "Q6") (pin "3") (pinfunction "C_3") (pintype "passive"))
      (node (ref "R36") (pin "2") (pinfunction "2_2") (pintype "passive"))
    )
    (net (code "65") (name "OUT6") (class "Default")
      (node (ref "J5") (pin "6") (pinfunction "6_6") (pintype "passive"))
      (node (ref "Q8") (pin "3") (pinfunction "C_3") (pintype "passive"))
      (node (ref "R37") (pin "2") (pinfunction "2_2") (pintype "passive"))
    )
    (net (code "66") (name "RESET") (class "Default")
      (node (ref "JP1") (pin "3") (pinfunction "3_3") (pintype "passive"))
      (node (ref "U$2") (pin "RST1") (pinfunction "RESET1_RST1") (pintype "bidirectional"))
    )
    (net (code "67") (name "RXI") (class "Default")
      (node (ref "JP1") (pin "5") (pinfunction "5_5") (pintype "passive"))
      (node (ref "U$2") (pin "RXI") (pinfunction "RXI_RXI") (pintype "bidirectional"))
    )
    (net (code "68") (name "TXO") (class "Default")
      (node (ref "JP1") (pin "4") (pinfunction "4_4") (pintype "passive"))
      (node (ref "U$2") (pin "TXO") (pinfunction "TXO_TXO") (pintype "bidirectional"))
    )
    (net (code "69") (name "VIN") (class "Default")
      (node (ref "D10") (pin "A") (pinfunction "A_A") (pintype "passive"))
      (node (ref "D9") (pin "C") (pinfunction "C_C") (pintype "passive"))
      (node (ref "J1") (pin "4") (pinfunction "4_4") (pintype "passive"))
      (node (ref "J1") (pin "5") (pinfunction "5_5") (pintype "passive"))
      (node (ref "J1") (pin "6") (pinfunction "6_6") (pintype "passive"))
      (node (ref "J2") (pin "6") (pinfunction "6_6") (pintype "passive"))
      (node (ref "JP1") (pin "2") (pinfunction "2_2") (pintype "passive"))
      (node (ref "Q9") (pin "3") (pinfunction "D_3") (pintype "bidirectional"))
    )
    (net (code "70") (name "unconnected-(U$2-PadCTS)") (class "Default")
      (node (ref "U$2") (pin "CTS") (pinfunction "CTS_CTS") (pintype "bidirectional"))
    )
    (net (code "71") (name "unconnected-(U$2-PadDTR)") (class "Default")
      (node (ref "U$2") (pin "DTR") (pinfunction "DTR_DTR") (pintype "bidirectional"))
    )
    (net (code "72") (name "unconnected-(U$2-PadGND4)") (class "Default")
      (node (ref "U$2") (pin "GND4") (pinfunction "GND4_GND4") (pintype "bidirectional"))
    )
    (net (code "73") (name "unconnected-(U$2-PadRAW)") (class "Default")
      (node (ref "U$2") (pin "RAW") (pinfunction "RAW_RAW") (pintype "bidirectional"))
    )
    (net (code "74") (name "unconnected-(U$2-PadRXI1)") (class "Default")
      (node (ref "U$2") (pin "RXI1") (pinfunction "RXI1_RXI1") (pintype "bidirectional"))
    )
    (net (code "75") (name "unconnected-(U$2-PadTXO1)") (class "Default")
      (node (ref "U$2") (pin "TXO1") (pinfunction "TXO1_TXO1") (pintype "bidirectional"))
    )
    (net (code "76") (name "unconnected-(U$2-PadVCC1)") (class "Default")
      (node (ref "U$2") (pin "VCC1") (pinfunction "VCC1_VCC1") (pintype "bidirectional"))
    )
    (net (code "77") (name "unconnected-(U$2-RESET-PadRST)") (class "Default")
      (node (ref "U$2") (pin "RST") (pinfunction "RESET_RST") (pintype "bidirectional"))
    )
  )
)
